# Motor_Controller.net
KiCad netlist of a schematic drawn in EAGLE
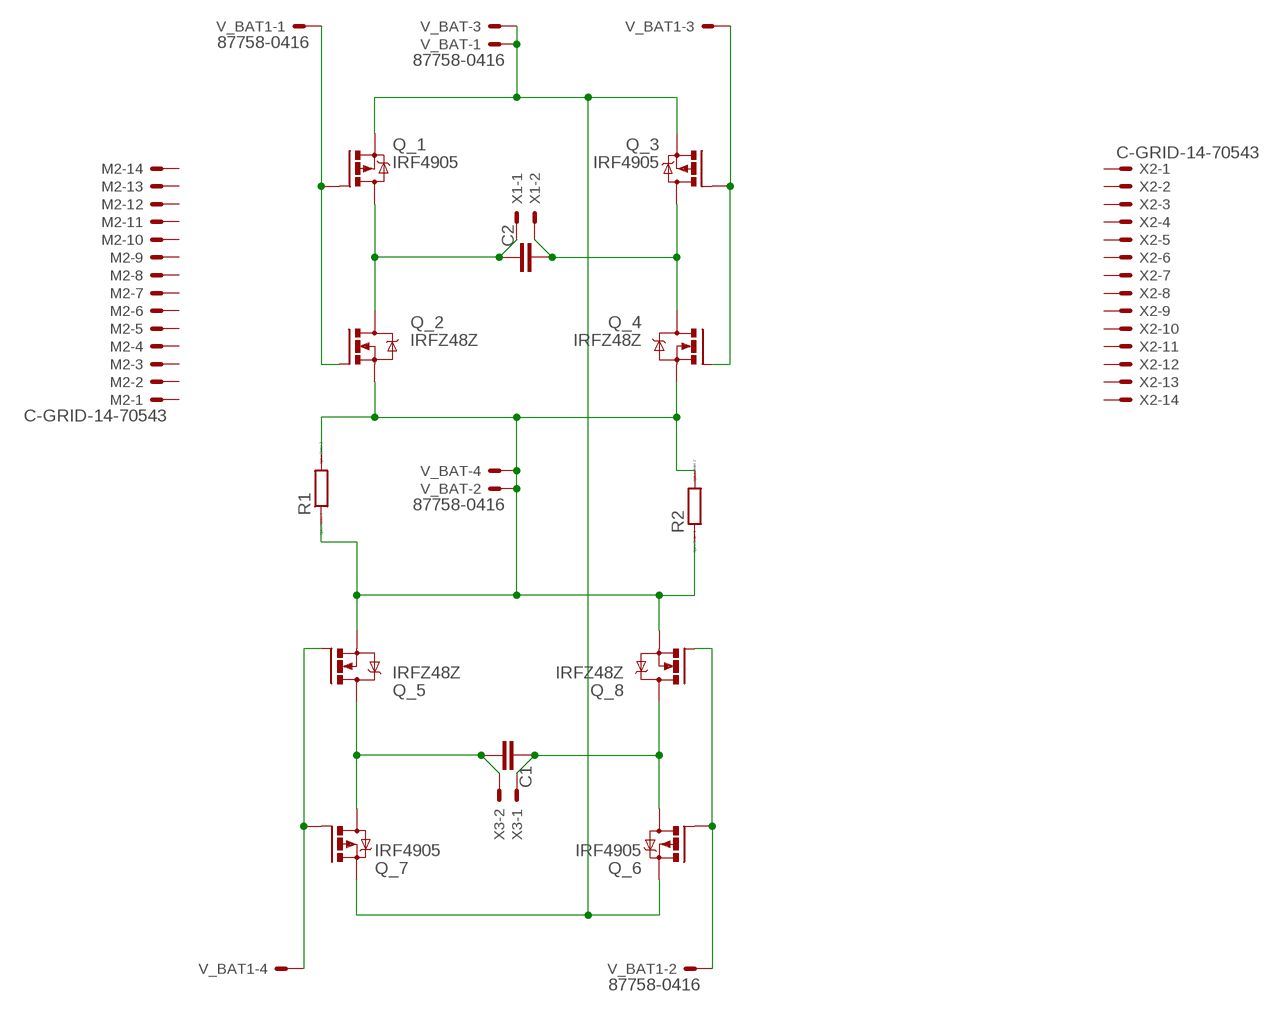
[diagram p0: schematic, sheet 1]

(export (version "E")
  (design (tool "Eeschema 10.0.6"))
  (components
    (comp (ref "C1")
      (value "C5/3")
      (footprint "eagle-import:C5B3")
      (libsource (lib "eagle-import") (part "C5/3"))
    )
    (comp (ref "C2")
      (value "C5/3")
      (footprint "eagle-import:C5B3")
      (libsource (lib "eagle-import") (part "C5/3"))
    )
    (comp (ref "M2")
      (value "C-GRID-14-70543")
      (footprint "eagle-import:70543-14")
      (libsource (lib "eagle-import") (part "C-GRID-14-70543"))
    )
    (comp (ref "Q_1")
      (value "IRF4905")
      (footprint "eagle-import:TO220BH")
      (libsource (lib "eagle-import") (part "IRF4905"))
    )
    (comp (ref "Q_2")
      (value "IRFZ48Z")
      (footprint "eagle-import:TO220BH")
      (libsource (lib "eagle-import") (part "IRFZ48Z"))
    )
    (comp (ref "Q_3")
      (value "IRF4905")
      (footprint "eagle-import:TO220BH")
      (libsource (lib "eagle-import") (part "IRF4905"))
    )
    (comp (ref "Q_4")
      (value "IRFZ48Z")
      (footprint "eagle-import:TO220BH")
      (libsource (lib "eagle-import") (part "IRFZ48Z"))
    )
    (comp (ref "Q_5")
      (value "IRFZ48Z")
      (footprint "eagle-import:TO220BH")
      (libsource (lib "eagle-import") (part "IRFZ48Z"))
    )
    (comp (ref "Q_6")
      (value "IRF4905")
      (footprint "eagle-import:TO220BH")
      (libsource (lib "eagle-import") (part "IRF4905"))
    )
    (comp (ref "Q_7")
      (value "IRF4905")
      (footprint "eagle-import:TO220BH")
      (libsource (lib "eagle-import") (part "IRF4905"))
    )
    (comp (ref "Q_8")
      (value "IRFZ48Z")
      (footprint "eagle-import:TO220BH")
      (libsource (lib "eagle-import") (part "IRFZ48Z"))
    )
    (comp (ref "R1")
      (value "R0204/7")
      (footprint "eagle-import:0204_7")
      (libsource (lib "eagle-import") (part "R0204/7"))
    )
    (comp (ref "R2")
      (value "R0204/7")
      (footprint "eagle-import:0204_7")
      (libsource (lib "eagle-import") (part "R0204/7"))
    )
    (comp (ref "V_BAT")
      (value "87758-0416")
      (footprint "eagle-import:87758-0416")
      (fields (field (name "MF") "FARNELL"))
      (libsource (lib "eagle-import") (part "87758-0416"))
    )
    (comp (ref "V_BAT1")
      (value "87758-0416")
      (footprint "eagle-import:87758-0416")
      (fields (field (name "MF") "FARNELL"))
      (libsource (lib "eagle-import") (part "87758-0416"))
    )
    (comp (ref "X1")
      (value "KK-156-2")
      (footprint "eagle-import:KK-156-2")
      (libsource (lib "eagle-import") (part "KK-156-2"))
    )
    (comp (ref "X2")
      (value "C-GRID-14-70543")
      (footprint "eagle-import:70543-14")
      (libsource (lib "eagle-import") (part "C-GRID-14-70543"))
    )
    (comp (ref "X3")
      (value "KK-156-2")
      (footprint "eagle-import:KK-156-2")
      (libsource (lib "eagle-import") (part "KK-156-2"))
    )
  )
  (nets
    (net (code "1") (name "Net-(V_BAT1A-S)") (class "Default")
      (node (ref "Q_1") (pin "G") (pinfunction "G_G") (pintype "passive"))
      (node (ref "Q_2") (pin "G") (pinfunction "G_G") (pintype "passive"))
      (node (ref "V_BAT1") (pin "1") (pinfunction "S_1") (pintype "passive"))
    )
    (net (code "2") (name "Net-(V_BAT1B-S)") (class "Default")
      (node (ref "Q_6") (pin "G") (pinfunction "G_G") (pintype "passive"))
      (node (ref "Q_8") (pin "G") (pinfunction "G_G") (pintype "passive"))
      (node (ref "V_BAT1") (pin "2") (pinfunction "S_2") (pintype "passive"))
    )
    (net (code "3") (name "Net-(V_BAT1C-S)") (class "Default")
      (node (ref "Q_3") (pin "G") (pinfunction "G_G") (pintype "passive"))
      (node (ref "Q_4") (pin "G") (pinfunction "G_G") (pintype "passive"))
      (node (ref "V_BAT1") (pin "3") (pinfunction "S_3") (pintype "passive"))
    )
    (net (code "4") (name "Net-(V_BAT1D-S)") (class "Default")
      (node (ref "Q_5") (pin "G") (pinfunction "G_G") (pintype "passive"))
      (node (ref "Q_7") (pin "G") (pinfunction "G_G") (pintype "passive"))
      (node (ref "V_BAT1") (pin "4") (pinfunction "S_4") (pintype "passive"))
    )
    (net (code "5") (name "Net-(V_BATA-S)") (class "Default")
      (node (ref "Q_1") (pin "S") (pinfunction "S_S") (pintype "passive"))
      (node (ref "Q_3") (pin "S") (pinfunction "S_S") (pintype "passive"))
      (node (ref "Q_6") (pin "S") (pinfunction "S_S") (pintype "passive"))
      (node (ref "Q_7") (pin "S") (pinfunction "S_S") (pintype "passive"))
      (node (ref "V_BAT") (pin "1") (pinfunction "S_1") (pintype "passive"))
      (node (ref "V_BAT") (pin "3") (pinfunction "S_3") (pintype "passive"))
    )
    (net (code "6") (name "Net-(V_BATB-S)") (class "Default")
      (node (ref "Q_2") (pin "S") (pinfunction "S_S") (pintype "passive"))
      (node (ref "Q_4") (pin "S") (pinfunction "S_S") (pintype "passive"))
      (node (ref "Q_5") (pin "S") (pinfunction "S_S") (pintype "passive"))
      (node (ref "Q_8") (pin "S") (pinfunction "S_S") (pintype "passive"))
      (node (ref "R1") (pin "1") (pinfunction "1_1") (pintype "passive"))
      (node (ref "R1") (pin "2") (pinfunction "2_2") (pintype "passive"))
      (node (ref "R2") (pin "1") (pinfunction "1_1") (pintype "passive"))
      (node (ref "R2") (pin "2") (pinfunction "2_2") (pintype "passive"))
      (node (ref "V_BAT") (pin "2") (pinfunction "S_2") (pintype "passive"))
      (node (ref "V_BAT") (pin "4") (pinfunction "S_4") (pintype "passive"))
    )
    (net (code "7") (name "Net-(X1A-S)") (class "Default")
      (node (ref "C2") (pin "1") (pinfunction "1_1") (pintype "passive"))
      (node (ref "Q_1") (pin "D") (pinfunction "D_D") (pintype "passive"))
      (node (ref "Q_2") (pin "D") (pinfunction "D_D") (pintype "passive"))
      (node (ref "X1") (pin "1") (pinfunction "S_1") (pintype "passive"))
    )
    (net (code "8") (name "Net-(X1B-S)") (class "Default")
      (node (ref "C2") (pin "2") (pinfunction "2_2") (pintype "passive"))
      (node (ref "Q_3") (pin "D") (pinfunction "D_D") (pintype "passive"))
      (node (ref "Q_4") (pin "D") (pinfunction "D_D") (pintype "passive"))
      (node (ref "X1") (pin "2") (pinfunction "S_2") (pintype "passive"))
    )
    (net (code "9") (name "Net-(X3A-S)") (class "Default")
      (node (ref "C1") (pin "1") (pinfunction "1_1") (pintype "passive"))
      (node (ref "Q_6") (pin "D") (pinfunction "D_D") (pintype "passive"))
      (node (ref "Q_8") (pin "D") (pinfunction "D_D") (pintype "passive"))
      (node (ref "X3") (pin "1") (pinfunction "S_1") (pintype "passive"))
    )
    (net (code "10") (name "Net-(X3B-S)") (class "Default")
      (node (ref "C1") (pin "2") (pinfunction "2_2") (pintype "passive"))
      (node (ref "Q_5") (pin "D") (pinfunction "D_D") (pintype "passive"))
      (node (ref "Q_7") (pin "D") (pinfunction "D_D") (pintype "passive"))
      (node (ref "X3") (pin "2") (pinfunction "S_2") (pintype "passive"))
    )
    (net (code "11") (name "unconnected-(M2A-S-Pad1)") (class "Default")
      (node (ref "M2") (pin "1") (pinfunction "S_1") (pintype "passive"))
    )
    (net (code "12") (name "unconnected-(M2B-S-Pad10)") (class "Default")
      (node (ref "M2") (pin "10") (pinfunction "S_10") (pintype "passive"))
    )
    (net (code "13") (name "unconnected-(M2C-S-Pad11)") (class "Default")
      (node (ref "M2") (pin "11") (pinfunction "S_11") (pintype "passive"))
    )
    (net (code "14") (name "unconnected-(M2D-S-Pad12)") (class "Default")
      (node (ref "M2") (pin "12") (pinfunction "S_12") (pintype "passive"))
    )
    (net (code "15") (name "unconnected-(M2E-S-Pad13)") (class "Default")
      (node (ref "M2") (pin "13") (pinfunction "S_13") (pintype "passive"))
    )
    (net (code "16") (name "unconnected-(M2F-S-Pad14)") (class "Default")
      (node (ref "M2") (pin "14") (pinfunction "S_14") (pintype "passive"))
    )
    (net (code "17") (name "unconnected-(M2G-S-Pad2)") (class "Default")
      (node (ref "M2") (pin "2") (pinfunction "S_2") (pintype "passive"))
    )
    (net (code "18") (name "unconnected-(M2H-S-Pad3)") (class "Default")
      (node (ref "M2") (pin "3") (pinfunction "S_3") (pintype "passive"))
    )
    (net (code "19") (name "unconnected-(M2I-S-Pad4)") (class "Default")
      (node (ref "M2") (pin "4") (pinfunction "S_4") (pintype "passive"))
    )
    (net (code "20") (name "unconnected-(M2J-S-Pad5)") (class "Default")
      (node (ref "M2") (pin "5") (pinfunction "S_5") (pintype "passive"))
    )
    (net (code "21") (name "unconnected-(M2K-S-Pad6)") (class "Default")
      (node (ref "M2") (pin "6") (pinfunction "S_6") (pintype "passive"))
    )
    (net (code "22") (name "unconnected-(M2L-S-Pad7)") (class "Default")
      (node (ref "M2") (pin "7") (pinfunction "S_7") (pintype "passive"))
    )
    (net (code "23") (name "unconnected-(M2M-S-Pad8)") (class "Default")
      (node (ref "M2") (pin "8") (pinfunction "S_8") (pintype "passive"))
    )
    (net (code "24") (name "unconnected-(M2N-S-Pad9)") (class "Default")
      (node (ref "M2") (pin "9") (pinfunction "S_9") (pintype "passive"))
    )
    (net (code "25") (name "unconnected-(X2A-S-Pad1)") (class "Default")
      (node (ref "X2") (pin "1") (pinfunction "S_1") (pintype "passive"))
    )
    (net (code "26") (name "unconnected-(X2B-S-Pad10)") (class "Default")
      (node (ref "X2") (pin "10") (pinfunction "S_10") (pintype "passive"))
    )
    (net (code "27") (name "unconnected-(X2C-S-Pad11)") (class "Default")
      (node (ref "X2") (pin "11") (pinfunction "S_11") (pintype "passive"))
    )
    (net (code "28") (name "unconnected-(X2D-S-Pad12)") (class "Default")
      (node (ref "X2") (pin "12") (pinfunction "S_12") (pintype "passive"))
    )
    (net (code "29") (name "unconnected-(X2E-S-Pad13)") (class "Default")
      (node (ref "X2") (pin "13") (pinfunction "S_13") (pintype "passive"))
    )
    (net (code "30") (name "unconnected-(X2F-S-Pad14)") (class "Default")
      (node (ref "X2") (pin "14") (pinfunction "S_14") (pintype "passive"))
    )
    (net (code "31") (name "unconnected-(X2G-S-Pad2)") (class "Default")
      (node (ref "X2") (pin "2") (pinfunction "S_2") (pintype "passive"))
    )
    (net (code "32") (name "unconnected-(X2H-S-Pad3)") (class "Default")
      (node (ref "X2") (pin "3") (pinfunction "S_3") (pintype "passive"))
    )
    (net (code "33") (name "unconnected-(X2I-S-Pad4)") (class "Default")
      (node (ref "X2") (pin "4") (pinfunction "S_4") (pintype "passive"))
    )
    (net (code "34") (name "unconnected-(X2J-S-Pad5)") (class "Default")
      (node (ref "X2") (pin "5") (pinfunction "S_5") (pintype "passive"))
    )
    (net (code "35") (name "unconnected-(X2K-S-Pad6)") (class "Default")
      (node (ref "X2") (pin "6") (pinfunction "S_6") (pintype "passive"))
    )
    (net (code "36") (name "unconnected-(X2L-S-Pad7)") (class "Default")
      (node (ref "X2") (pin "7") (pinfunction "S_7") (pintype "passive"))
    )
    (net (code "37") (name "unconnected-(X2M-S-Pad8)") (class "Default")
      (node (ref "X2") (pin "8") (pinfunction "S_8") (pintype "passive"))
    )
    (net (code "38") (name "unconnected-(X2N-S-Pad9)") (class "Default")
      (node (ref "X2") (pin "9") (pinfunction "S_9") (pintype "passive"))
    )
  )
)
